# ISOW7840DWE.net
KiCad netlist of a schematic drawn in Altium Designer
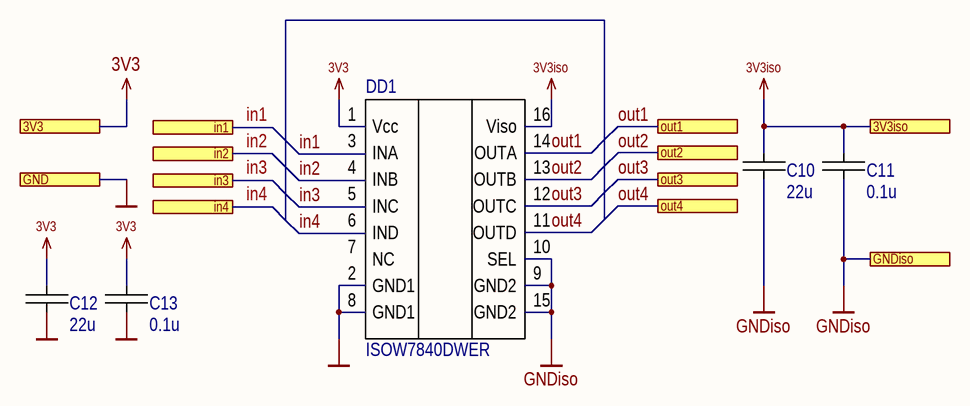
[diagram p0: ISOW7840DWE.SchDoc]

(export (version "E")
  (design (tool "Eeschema 10.0.6"))
  (components
    (comp (ref "C10")
      (value "22u")
      (footprint "C0805_IPC")
      (description "22µF ±20% 6.3V Ceramic Capacitor X5R 0805 (2012 Metric)")
      (fields (field (name "MPN") "CL21A226MQQNNNE") (field (name "TOLERANCE") "0.2"))
      (libsource (lib "DB_res_cap_ind") (part "C0805_GOST"))
    )
    (comp (ref "C11")
      (value "0.1u")
      (footprint "C0603_IPC")
      (description "0.1uF ±10% 50V Ceramic Capacitor X7R 0603 (1608 Metric)")
      (fields (field (name "MPN") "CL10B104KB8NNND") (field (name "TOLERANCE") "0,1"))
      (libsource (lib "DB_res_cap_ind") (part "C0603_GOST"))
    )
    (comp (ref "C12")
      (value "22u")
      (footprint "C0805_IPC")
      (description "22µF ±20% 6.3V Ceramic Capacitor X5R 0805 (2012 Metric)")
      (fields (field (name "MPN") "CL21A226MQQNNNE") (field (name "TOLERANCE") "0.2"))
      (libsource (lib "DB_res_cap_ind") (part "C0805_GOST"))
    )
    (comp (ref "C13")
      (value "0.1u")
      (footprint "C0603_IPC")
      (description "0.1uF ±10% 50V Ceramic Capacitor X7R 0603 (1608 Metric)")
      (fields (field (name "MPN") "CL10B104KB8NNND") (field (name "TOLERANCE") "0,1"))
      (libsource (lib "DB_res_cap_ind") (part "C0603_GOST"))
    )
    (comp (ref "DD1")
      (value "ISOW7840DWER")
      (footprint "SOIC16W")
      (fields (field (name "MANUFACTURER") "Texas Instruments"))
      (libsource (lib "DB_IC") (part "ISOW7840DWER"))
    )
  )
  (nets
    (net (code "2") (name "/out1") (class "Default")
      (node (ref "DD1") (pin "14") (pinfunction "OUTA_14") (pintype "passive"))
    )
    (net (code "3") (name "/out2") (class "Default")
      (node (ref "DD1") (pin "13") (pinfunction "OUTB_13") (pintype "passive"))
    )
    (net (code "4") (name "/out3") (class "Default")
      (node (ref "DD1") (pin "12") (pinfunction "OUTC_12") (pintype "passive"))
    )
    (net (code "5") (name "/out4") (class "Default")
      (node (ref "DD1") (pin "11") (pinfunction "OUTD_11") (pintype "passive"))
    )
    (net (code "6") (name "3V3") (class "Default")
      (node (ref "C12") (pin "1") (pinfunction "1_1") (pintype "passive"))
      (node (ref "C13") (pin "1") (pinfunction "1_1") (pintype "passive"))
      (node (ref "DD1") (pin "1") (pinfunction "Vcc_1") (pintype "passive"))
    )
    (net (code "7") (name "3V3iso") (class "Default")
      (node (ref "C10") (pin "1") (pinfunction "1_1") (pintype "passive"))
      (node (ref "C11") (pin "1") (pinfunction "1_1") (pintype "passive"))
      (node (ref "DD1") (pin "16") (pinfunction "Viso_16") (pintype "passive"))
    )
    (net (code "8") (name "GND") (class "Default")
      (node (ref "C12") (pin "2") (pinfunction "2_2") (pintype "passive"))
      (node (ref "C13") (pin "2") (pinfunction "2_2") (pintype "passive"))
      (node (ref "DD1") (pin "2") (pinfunction "GND1_2") (pintype "passive"))
      (node (ref "DD1") (pin "8") (pinfunction "GND1_8") (pintype "passive"))
    )
    (net (code "9") (name "GNDiso") (class "Default")
      (node (ref "C10") (pin "2") (pinfunction "2_2") (pintype "passive"))
      (node (ref "C11") (pin "2") (pinfunction "2_2") (pintype "passive"))
      (node (ref "DD1") (pin "10") (pinfunction "SEL_10") (pintype "passive"))
      (node (ref "DD1") (pin "15") (pinfunction "GND2_15") (pintype "passive"))
      (node (ref "DD1") (pin "9") (pinfunction "GND2_9") (pintype "passive"))
    )
    (net (code "10") (name "unconnected-(DD1-INA-Pad3)") (class "Default")
      (node (ref "DD1") (pin "3") (pinfunction "INA_3") (pintype "passive"))
    )
    (net (code "11") (name "unconnected-(DD1-INB-Pad4)") (class "Default")
      (node (ref "DD1") (pin "4") (pinfunction "INB_4") (pintype "passive"))
    )
    (net (code "12") (name "unconnected-(DD1-INC-Pad5)") (class "Default")
      (node (ref "DD1") (pin "5") (pinfunction "INC_5") (pintype "passive"))
    )
    (net (code "13") (name "unconnected-(DD1-IND-Pad6)") (class "Default")
      (node (ref "DD1") (pin "6") (pinfunction "IND_6") (pintype "passive"))
    )
    (net (code "14") (name "unconnected-(DD1-NC-Pad1)") (class "Default")
      (node (ref "DD1") (pin "1") (pinfunction "NC_1") (pintype "passive"))
    )
    (net (code "15") (name "unconnected-(DD1-NC-Pad2)") (class "Default")
      (node (ref "DD1") (pin "2") (pinfunction "NC_2") (pintype "tri_state"))
    )
    (net (code "16") (name "unconnected-(DD1-NC-Pad7)") (class "Default")
      (node (ref "DD1") (pin "7") (pinfunction "NC_7") (pintype "passive"))
    )
  )
)
